# schematic.net
KiCad netlist of a schematic drawn in EAGLE
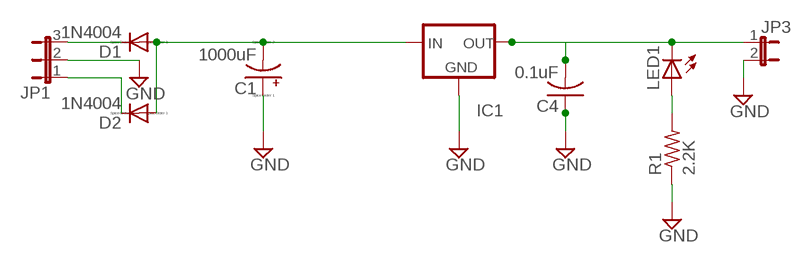
[diagram p0: schematic, sheet 1]

(export (version "E")
  (design (tool "Eeschema 10.0.6"))
  (components
    (comp (ref "C1")
      (value "1000uF")
      (footprint "eagle-import:E5-10,5")
      (libsource (lib "eagle-import") (part "CPOL-USE5-10.5"))
    )
    (comp (ref "C4")
      (value "0.1uF")
      (footprint "eagle-import:C050-025X075")
      (libsource (lib "eagle-import") (part "C-US050-025X075"))
    )
    (comp (ref "D1")
      (value "1N4004")
      (footprint "eagle-import:DO41-10")
      (libsource (lib "eagle-import") (part "1N4004"))
    )
    (comp (ref "D2")
      (value "1N4004")
      (footprint "eagle-import:DO41-10")
      (libsource (lib "eagle-import") (part "1N4004"))
    )
    (comp (ref "IC1")
      (value "79XXS")
      (footprint "eagle-import:79XXS")
      (libsource (lib "eagle-import") (part "79XXS"))
    )
    (comp (ref "JP1")
      (value "JP2E")
      (footprint "eagle-import:JP2")
      (libsource (lib "eagle-import") (part "JP2E"))
    )
    (comp (ref "JP3")
      (value "JP1E")
      (footprint "eagle-import:JP1")
      (libsource (lib "eagle-import") (part "JP1E"))
    )
    (comp (ref "LED1")
      (value "LED5MM")
      (footprint "eagle-import:LED5MM")
      (libsource (lib "eagle-import") (part "LED5MM"))
    )
    (comp (ref "R1")
      (value "2.2K")
      (footprint "eagle-import:0309_12")
      (libsource (lib "eagle-import") (part "R-US_0309/12"))
    )
  )
  (nets
    (net (code "1") (name "GND") (class "Default")
      (node (ref "C1") (pin "+") (pinfunction "+_+") (pintype "passive"))
      (node (ref "C4") (pin "1") (pinfunction "1_1") (pintype "passive"))
      (node (ref "IC1") (pin "GND") (pinfunction "GND_GND") (pintype "input"))
      (node (ref "JP1") (pin "2") (pinfunction "2_2") (pintype "passive"))
      (node (ref "JP3") (pin "2") (pinfunction "2_2") (pintype "passive"))
      (node (ref "R1") (pin "1") (pinfunction "1_1") (pintype "passive"))
    )
    (net (code "2") (name "Net-(C1-Pad-)") (class "Default")
      (node (ref "C1") (pin "-") (pinfunction "-_-") (pintype "passive"))
      (node (ref "D1") (pin "A") (pinfunction "A_A") (pintype "passive"))
      (node (ref "D2") (pin "A") (pinfunction "A_A") (pintype "passive"))
      (node (ref "IC1") (pin "IN") (pinfunction "IN_IN") (pintype "input"))
    )
    (net (code "3") (name "Net-(D1-PadC)") (class "Default")
      (node (ref "D1") (pin "C") (pinfunction "C_C") (pintype "passive"))
      (node (ref "JP1") (pin "3") (pinfunction "3_3") (pintype "passive"))
    )
    (net (code "4") (name "Net-(D2-PadC)") (class "Default")
      (node (ref "D2") (pin "C") (pinfunction "C_C") (pintype "passive"))
      (node (ref "JP1") (pin "1") (pinfunction "1_1") (pintype "passive"))
    )
    (net (code "5") (name "Net-(LED1-C)") (class "Default")
      (node (ref "C4") (pin "2") (pinfunction "2_2") (pintype "passive"))
      (node (ref "IC1") (pin "OUT") (pinfunction "OUT_OUT") (pintype "passive"))
      (node (ref "JP3") (pin "1") (pinfunction "1_1") (pintype "passive"))
      (node (ref "LED1") (pin "K") (pinfunction "C_K") (pintype "passive"))
    )
    (net (code "6") (name "Net-(LED1-PadA)") (class "Default")
      (node (ref "LED1") (pin "A") (pinfunction "A_A") (pintype "passive"))
      (node (ref "R1") (pin "2") (pinfunction "2_2") (pintype "passive"))
    )
  )
)
